# TeilerPlatine.net
KiCad netlist of a schematic drawn in EAGLE
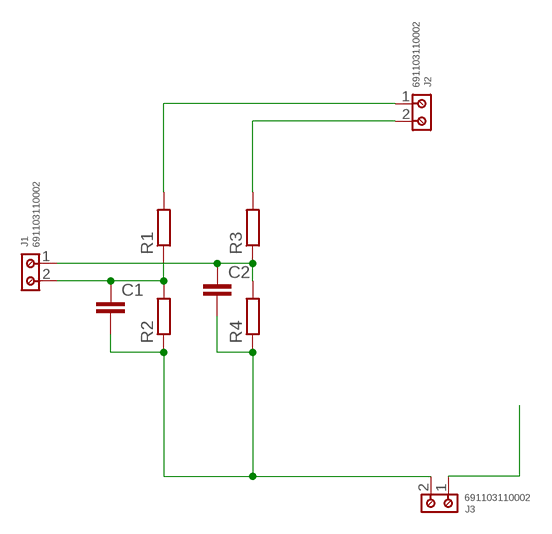
[diagram p0: schematic, sheet 1]

(export (version "E")
  (design (tool "Eeschema 10.0.6"))
  (components
    (comp (ref "C1")
      (value "C-EU050-025X075")
      (footprint "eagle-import:C050-025X075")
      (libsource (lib "eagle-import") (part "C-EU050-025X075"))
    )
    (comp (ref "C2")
      (value "C-EU050-025X075")
      (footprint "eagle-import:C050-025X075")
      (libsource (lib "eagle-import") (part "C-EU050-025X075"))
    )
    (comp (ref "J1")
      (value "691103110002")
      (footprint "eagle-import:691103110002")
      (libsource (lib "eagle-import") (part "691103110002"))
    )
    (comp (ref "J2")
      (value "691103110002")
      (footprint "eagle-import:691103110002")
      (libsource (lib "eagle-import") (part "691103110002"))
    )
    (comp (ref "J3")
      (value "691103110002")
      (footprint "eagle-import:691103110002")
      (libsource (lib "eagle-import") (part "691103110002"))
    )
    (comp (ref "R1")
      (value "R-EU_0411/15")
      (footprint "eagle-import:0411_15")
      (libsource (lib "eagle-import") (part "R-EU_0411/15"))
    )
    (comp (ref "R2")
      (value "R-EU_0411/15")
      (footprint "eagle-import:0411_15")
      (libsource (lib "eagle-import") (part "R-EU_0411/15"))
    )
    (comp (ref "R3")
      (value "R-EU_0411/15")
      (footprint "eagle-import:0411_15")
      (libsource (lib "eagle-import") (part "R-EU_0411/15"))
    )
    (comp (ref "R4")
      (value "R-EU_0411/15")
      (footprint "eagle-import:0411_15")
      (libsource (lib "eagle-import") (part "R-EU_0411/15"))
    )
  )
  (nets
    (net (code "1") (name "Net-(C1-Pad1)") (class "Default")
      (node (ref "C1") (pin "1") (pinfunction "1_1") (pintype "passive"))
      (node (ref "J1") (pin "2") (pinfunction "2_2") (pintype "passive"))
      (node (ref "R1") (pin "1") (pinfunction "1_1") (pintype "passive"))
      (node (ref "R2") (pin "2") (pinfunction "2_2") (pintype "passive"))
    )
    (net (code "2") (name "Net-(C1-Pad2)") (class "Default")
      (node (ref "C1") (pin "2") (pinfunction "2_2") (pintype "passive"))
      (node (ref "C2") (pin "2") (pinfunction "2_2") (pintype "passive"))
      (node (ref "J3") (pin "2") (pinfunction "2_2") (pintype "passive"))
      (node (ref "R2") (pin "1") (pinfunction "1_1") (pintype "passive"))
      (node (ref "R4") (pin "1") (pinfunction "1_1") (pintype "passive"))
    )
    (net (code "3") (name "Net-(C2-Pad1)") (class "Default")
      (node (ref "C2") (pin "1") (pinfunction "1_1") (pintype "passive"))
      (node (ref "J1") (pin "1") (pinfunction "1_1") (pintype "passive"))
      (node (ref "R3") (pin "1") (pinfunction "1_1") (pintype "passive"))
      (node (ref "R4") (pin "2") (pinfunction "2_2") (pintype "passive"))
    )
    (net (code "4") (name "Net-(J2-Pad1)") (class "Default")
      (node (ref "J2") (pin "1") (pinfunction "1_1") (pintype "passive"))
      (node (ref "R1") (pin "2") (pinfunction "2_2") (pintype "passive"))
    )
    (net (code "5") (name "Net-(J2-Pad2)") (class "Default")
      (node (ref "J2") (pin "2") (pinfunction "2_2") (pintype "passive"))
      (node (ref "R3") (pin "2") (pinfunction "2_2") (pintype "passive"))
    )
    (net (code "6") (name "unconnected-(J3-Pad1)") (class "Default")
      (node (ref "J3") (pin "1") (pinfunction "1_1") (pintype "passive"))
    )
  )
)
